# Digital_Fanout.net
KiCad netlist of a schematic drawn in Altium Designer
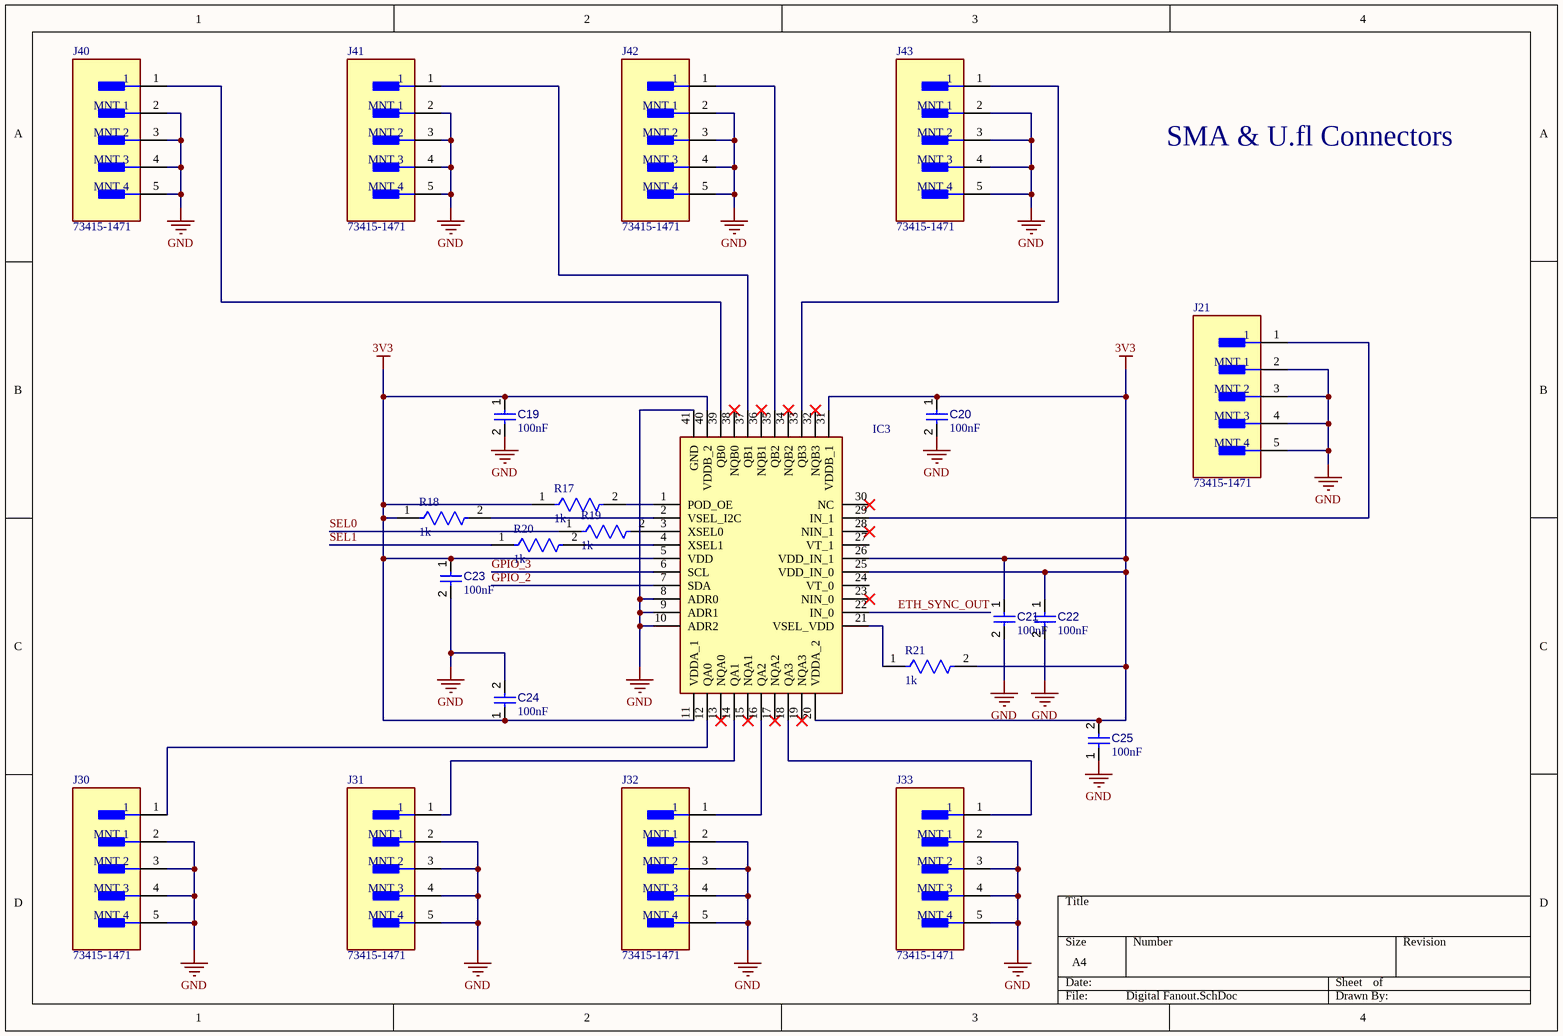
[diagram p0: Digital Fanout.SchDoc]

(export (version "E")
  (design (tool "Eeschema 10.0.6"))
  (components
    (comp (ref "C19")
      (value "100nF")
      (footprint "CAPC0402(1005)60_L")
      (description "Chip Capacitor, 100nF +/-20%, 25V, 0402, Thickness 0.6 mm")
      (fields (field (name "TOLERANCE") "10%") (field (name "Comment") "Capacitor 100nF +/-20% 25V 0402"))
      (libsource (lib "Lasse Johnsen") (part "CAP-NP-2"))
    )
    (comp (ref "C20")
      (value "100nF")
      (footprint "CAPC0402(1005)60_L")
      (description "Chip Capacitor, 100nF +/-20%, 25V, 0402, Thickness 0.6 mm")
      (fields (field (name "TOLERANCE") "10%") (field (name "Comment") "Capacitor 100nF +/-20% 25V 0402"))
      (libsource (lib "Lasse Johnsen") (part "CAP-NP-2"))
    )
    (comp (ref "C21")
      (value "100nF")
      (footprint "CAPC0402(1005)60_L")
      (description "Chip Capacitor, 100nF +/-20%, 25V, 0402, Thickness 0.6 mm")
      (fields (field (name "TOLERANCE") "10%") (field (name "Comment") "Capacitor 100nF +/-20% 25V 0402"))
      (libsource (lib "Lasse Johnsen") (part "CAP-NP-2"))
    )
    (comp (ref "C22")
      (value "100nF")
      (footprint "CAPC0402(1005)60_L")
      (description "Chip Capacitor, 100nF +/-20%, 25V, 0402, Thickness 0.6 mm")
      (fields (field (name "TOLERANCE") "10%") (field (name "Comment") "Capacitor 100nF +/-20% 25V 0402"))
      (libsource (lib "Lasse Johnsen") (part "CAP-NP-2"))
    )
    (comp (ref "C23")
      (value "100nF")
      (footprint "CAPC0402(1005)60_L")
      (description "Chip Capacitor, 100nF +/-20%, 25V, 0402, Thickness 0.6 mm")
      (fields (field (name "TOLERANCE") "10%") (field (name "Comment") "Capacitor 100nF +/-20% 25V 0402"))
      (libsource (lib "Lasse Johnsen") (part "CAP-NP-2"))
    )
    (comp (ref "C24")
      (value "100nF")
      (footprint "CAPC0402(1005)60_L")
      (description "Chip Capacitor, 100nF +/-20%, 25V, 0402, Thickness 0.6 mm")
      (fields (field (name "TOLERANCE") "10%") (field (name "Comment") "Capacitor 100nF +/-20% 25V 0402"))
      (libsource (lib "Lasse Johnsen") (part "CAP-NP-2"))
    )
    (comp (ref "C25")
      (value "100nF")
      (footprint "CAPC0402(1005)60_L")
      (description "Chip Capacitor, 100nF +/-20%, 25V, 0402, Thickness 0.6 mm")
      (fields (field (name "TOLERANCE") "10%") (field (name "Comment") "Capacitor 100nF +/-20% 25V 0402"))
      (libsource (lib "Lasse Johnsen") (part "CAP-NP-2"))
    )
    (comp (ref "IC3")
      (value "8T79S308NLGI")
      (footprint "SamacSys:QFN50P600X600X100-41N")
      (description "Integrated Circuit")
      (fields (field (name "MOUSER PART NUMBER") "972-8T79S308NLGI"))
      (libsource (lib "*") (part "8T79S308NLGI"))
    )
    (comp (ref "J21")
      (value "73415-1471")
      (footprint "FP-73415-1471-MFG")
      (description "CONN MMCX JACK STR 50 OHM PCB")
      (fields
        (field (name "MANUFACTURER") "Molex")
        (field (name "OCTOPART") "https://octopart.com/73415-1471-molex-776288")
      )
      (libsource (lib "Altium Content Vault") (part "e24f7cd101112e4466c0a3e46d8e956"))
    )
    (comp (ref "J30")
      (value "73415-1471")
      (footprint "FP-73415-1471-MFG")
      (description "CONN MMCX JACK STR 50 OHM PCB")
      (fields
        (field (name "MANUFACTURER") "Molex")
        (field (name "OCTOPART") "https://octopart.com/73415-1471-molex-776288")
      )
      (libsource (lib "Altium Content Vault") (part "e24f7cd101112e4466c0a3e46d8e956"))
    )
    (comp (ref "J31")
      (value "73415-1471")
      (footprint "FP-73415-1471-MFG")
      (description "CONN MMCX JACK STR 50 OHM PCB")
      (fields
        (field (name "MANUFACTURER") "Molex")
        (field (name "OCTOPART") "https://octopart.com/73415-1471-molex-776288")
      )
      (libsource (lib "Altium Content Vault") (part "e24f7cd101112e4466c0a3e46d8e956"))
    )
    (comp (ref "J32")
      (value "73415-1471")
      (footprint "FP-73415-1471-MFG")
      (description "CONN MMCX JACK STR 50 OHM PCB")
      (fields
        (field (name "MANUFACTURER") "Molex")
        (field (name "OCTOPART") "https://octopart.com/73415-1471-molex-776288")
      )
      (libsource (lib "Altium Content Vault") (part "e24f7cd101112e4466c0a3e46d8e956"))
    )
    (comp (ref "J33")
      (value "73415-1471")
      (footprint "FP-73415-1471-MFG")
      (description "CONN MMCX JACK STR 50 OHM PCB")
      (fields
        (field (name "MANUFACTURER") "Molex")
        (field (name "OCTOPART") "https://octopart.com/73415-1471-molex-776288")
      )
      (libsource (lib "Altium Content Vault") (part "e24f7cd101112e4466c0a3e46d8e956"))
    )
    (comp (ref "J40")
      (value "73415-1471")
      (footprint "FP-73415-1471-MFG")
      (description "CONN MMCX JACK STR 50 OHM PCB")
      (fields
        (field (name "MANUFACTURER") "Molex")
        (field (name "OCTOPART") "https://octopart.com/73415-1471-molex-776288")
      )
      (libsource (lib "Altium Content Vault") (part "e24f7cd101112e4466c0a3e46d8e956"))
    )
    (comp (ref "J41")
      (value "73415-1471")
      (footprint "FP-73415-1471-MFG")
      (description "CONN MMCX JACK STR 50 OHM PCB")
      (fields
        (field (name "MANUFACTURER") "Molex")
        (field (name "OCTOPART") "https://octopart.com/73415-1471-molex-776288")
      )
      (libsource (lib "Altium Content Vault") (part "e24f7cd101112e4466c0a3e46d8e956"))
    )
    (comp (ref "J42")
      (value "73415-1471")
      (footprint "FP-73415-1471-MFG")
      (description "CONN MMCX JACK STR 50 OHM PCB")
      (fields
        (field (name "MANUFACTURER") "Molex")
        (field (name "OCTOPART") "https://octopart.com/73415-1471-molex-776288")
      )
      (libsource (lib "Altium Content Vault") (part "e24f7cd101112e4466c0a3e46d8e956"))
    )
    (comp (ref "J43")
      (value "73415-1471")
      (footprint "FP-73415-1471-MFG")
      (description "CONN MMCX JACK STR 50 OHM PCB")
      (fields
        (field (name "MANUFACTURER") "Molex")
        (field (name "OCTOPART") "https://octopart.com/73415-1471-molex-776288")
      )
      (libsource (lib "Altium Content Vault") (part "e24f7cd101112e4466c0a3e46d8e956"))
    )
    (comp (ref "R17")
      (value "1k")
      (footprint "FP-CRCW0402-e3-MFG")
      (description "RES Thick Film, 1kΩ, 1%, 0.063W, 100ppm/°C, 0402")
      (fields (field (name "TOLERANCE") "1%"))
      (libsource (lib "Altium Content Vault") (part "1029c3af85768c4190bb7ad29bc67b5"))
    )
    (comp (ref "R18")
      (value "1k")
      (footprint "FP-CRCW0402-e3-MFG")
      (description "RES Thick Film, 1kΩ, 1%, 0.063W, 100ppm/°C, 0402")
      (fields (field (name "TOLERANCE") "1%"))
      (libsource (lib "Altium Content Vault") (part "1029c3af85768c4190bb7ad29bc67b5"))
    )
    (comp (ref "R19")
      (value "1k")
      (footprint "FP-CRCW0402-e3-MFG")
      (description "RES Thick Film, 1kΩ, 1%, 0.063W, 100ppm/°C, 0402")
      (fields (field (name "TOLERANCE") "1%"))
      (libsource (lib "Altium Content Vault") (part "1029c3af85768c4190bb7ad29bc67b5"))
    )
    (comp (ref "R20")
      (value "1k")
      (footprint "FP-CRCW0402-e3-MFG")
      (description "RES Thick Film, 1kΩ, 1%, 0.063W, 100ppm/°C, 0402")
      (fields (field (name "TOLERANCE") "1%"))
      (libsource (lib "Altium Content Vault") (part "1029c3af85768c4190bb7ad29bc67b5"))
    )
    (comp (ref "R21")
      (value "1k")
      (footprint "FP-CRCW0402-e3-MFG")
      (description "RES Thick Film, 1kΩ, 1%, 0.063W, 100ppm/°C, 0402")
      (fields (field (name "TOLERANCE") "1%"))
      (libsource (lib "Altium Content Vault") (part "1029c3af85768c4190bb7ad29bc67b5"))
    )
  )
  (nets
    (net (code "1") (name "/ETH_SYNC_OUT") (class "Default")
      (node (ref "IC3") (pin "22") (pinfunction "IN_0_22") (pintype "passive"))
    )
    (net (code "2") (name "/GPIO_2") (class "Default")
      (node (ref "IC3") (pin "7") (pinfunction "SDA_7") (pintype "passive"))
    )
    (net (code "3") (name "/GPIO_3") (class "Default")
      (node (ref "IC3") (pin "6") (pinfunction "SCL_6") (pintype "passive"))
    )
    (net (code "4") (name "/SEL0") (class "Default")
      (node (ref "R19") (pin "1") (pinfunction "1_1") (pintype "passive"))
    )
    (net (code "5") (name "/SEL1") (class "Default")
      (node (ref "R20") (pin "1") (pinfunction "1_1") (pintype "passive"))
    )
    (net (code "6") (name "3V3") (class "Default")
      (node (ref "C19") (pin "1") (pinfunction "1_1") (pintype "passive"))
      (node (ref "C20") (pin "1") (pinfunction "1_1") (pintype "passive"))
      (node (ref "C21") (pin "1") (pinfunction "1_1") (pintype "passive"))
      (node (ref "C22") (pin "1") (pinfunction "1_1") (pintype "passive"))
      (node (ref "C23") (pin "1") (pinfunction "1_1") (pintype "passive"))
      (node (ref "C24") (pin "1") (pinfunction "1_1") (pintype "passive"))
      (node (ref "C25") (pin "2") (pinfunction "2_2") (pintype "passive"))
      (node (ref "IC3") (pin "11") (pinfunction "VDDA_1_11") (pintype "passive"))
      (node (ref "IC3") (pin "20") (pinfunction "VDDA_2_20") (pintype "passive"))
      (node (ref "IC3") (pin "25") (pinfunction "VDD_IN_0_25") (pintype "passive"))
      (node (ref "IC3") (pin "26") (pinfunction "VDD_IN_1_26") (pintype "passive"))
      (node (ref "IC3") (pin "31") (pinfunction "VDDB_1_31") (pintype "passive"))
      (node (ref "IC3") (pin "40") (pinfunction "VDDB_2_40") (pintype "passive"))
      (node (ref "IC3") (pin "5") (pinfunction "VDD_5") (pintype "passive"))
      (node (ref "R17") (pin "1") (pinfunction "1_1") (pintype "passive"))
      (node (ref "R18") (pin "1") (pinfunction "1_1") (pintype "passive"))
      (node (ref "R21") (pin "2") (pinfunction "2_2") (pintype "passive"))
    )
    (net (code "7") (name "GND") (class "Default")
      (node (ref "C19") (pin "2") (pinfunction "2_2") (pintype "passive"))
      (node (ref "C20") (pin "2") (pinfunction "2_2") (pintype "passive"))
      (node (ref "C21") (pin "2") (pinfunction "2_2") (pintype "passive"))
      (node (ref "C22") (pin "2") (pinfunction "2_2") (pintype "passive"))
      (node (ref "C23") (pin "2") (pinfunction "2_2") (pintype "passive"))
      (node (ref "C24") (pin "2") (pinfunction "2_2") (pintype "passive"))
      (node (ref "C25") (pin "1") (pinfunction "1_1") (pintype "passive"))
      (node (ref "IC3") (pin "10") (pinfunction "ADR2_10") (pintype "passive"))
      (node (ref "IC3") (pin "41") (pinfunction "GND_41") (pintype "passive"))
      (node (ref "IC3") (pin "8") (pinfunction "ADR0_8") (pintype "passive"))
      (node (ref "IC3") (pin "9") (pinfunction "ADR1_9") (pintype "passive"))
      (node (ref "J21") (pin "2") (pinfunction "MNT_1_2") (pintype "passive"))
      (node (ref "J21") (pin "3") (pinfunction "MNT_2_3") (pintype "passive"))
      (node (ref "J21") (pin "4") (pinfunction "MNT_3_4") (pintype "passive"))
      (node (ref "J21") (pin "5") (pinfunction "MNT_4_5") (pintype "passive"))
      (node (ref "J30") (pin "2") (pinfunction "MNT_1_2") (pintype "passive"))
      (node (ref "J30") (pin "3") (pinfunction "MNT_2_3") (pintype "passive"))
      (node (ref "J30") (pin "4") (pinfunction "MNT_3_4") (pintype "passive"))
      (node (ref "J30") (pin "5") (pinfunction "MNT_4_5") (pintype "passive"))
      (node (ref "J31") (pin "2") (pinfunction "MNT_1_2") (pintype "passive"))
      (node (ref "J31") (pin "3") (pinfunction "MNT_2_3") (pintype "passive"))
      (node (ref "J31") (pin "4") (pinfunction "MNT_3_4") (pintype "passive"))
      (node (ref "J31") (pin "5") (pinfunction "MNT_4_5") (pintype "passive"))
      (node (ref "J32") (pin "2") (pinfunction "MNT_1_2") (pintype "passive"))
      (node (ref "J32") (pin "3") (pinfunction "MNT_2_3") (pintype "passive"))
      (node (ref "J32") (pin "4") (pinfunction "MNT_3_4") (pintype "passive"))
      (node (ref "J32") (pin "5") (pinfunction "MNT_4_5") (pintype "passive"))
      (node (ref "J33") (pin "2") (pinfunction "MNT_1_2") (pintype "passive"))
      (node (ref "J33") (pin "3") (pinfunction "MNT_2_3") (pintype "passive"))
      (node (ref "J33") (pin "4") (pinfunction "MNT_3_4") (pintype "passive"))
      (node (ref "J33") (pin "5") (pinfunction "MNT_4_5") (pintype "passive"))
      (node (ref "J40") (pin "2") (pinfunction "MNT_1_2") (pintype "passive"))
      (node (ref "J40") (pin "3") (pinfunction "MNT_2_3") (pintype "passive"))
      (node (ref "J40") (pin "4") (pinfunction "MNT_3_4") (pintype "passive"))
      (node (ref "J40") (pin "5") (pinfunction "MNT_4_5") (pintype "passive"))
      (node (ref "J41") (pin "2") (pinfunction "MNT_1_2") (pintype "passive"))
      (node (ref "J41") (pin "3") (pinfunction "MNT_2_3") (pintype "passive"))
      (node (ref "J41") (pin "4") (pinfunction "MNT_3_4") (pintype "passive"))
      (node (ref "J41") (pin "5") (pinfunction "MNT_4_5") (pintype "passive"))
      (node (ref "J42") (pin "2") (pinfunction "MNT_1_2") (pintype "passive"))
      (node (ref "J42") (pin "3") (pinfunction "MNT_2_3") (pintype "passive"))
      (node (ref "J42") (pin "4") (pinfunction "MNT_3_4") (pintype "passive"))
      (node (ref "J42") (pin "5") (pinfunction "MNT_4_5") (pintype "passive"))
      (node (ref "J43") (pin "2") (pinfunction "MNT_1_2") (pintype "passive"))
      (node (ref "J43") (pin "3") (pinfunction "MNT_2_3") (pintype "passive"))
      (node (ref "J43") (pin "4") (pinfunction "MNT_3_4") (pintype "passive"))
      (node (ref "J43") (pin "5") (pinfunction "MNT_4_5") (pintype "passive"))
    )
    (net (code "8") (name "Net-(IC3-IN_1)") (class "Default")
      (node (ref "IC3") (pin "29") (pinfunction "IN_1_29") (pintype "passive"))
      (node (ref "J21") (pin "1") (pinfunction "1_1") (pintype "passive"))
    )
    (net (code "9") (name "Net-(IC3-POD_OE)") (class "Default")
      (node (ref "IC3") (pin "1") (pinfunction "POD_OE_1") (pintype "passive"))
      (node (ref "R17") (pin "2") (pinfunction "2_2") (pintype "passive"))
    )
    (net (code "10") (name "Net-(IC3-QA0)") (class "Default")
      (node (ref "IC3") (pin "12") (pinfunction "QA0_12") (pintype "passive"))
      (node (ref "J30") (pin "1") (pinfunction "1_1") (pintype "passive"))
    )
    (net (code "11") (name "Net-(IC3-QA1)") (class "Default")
      (node (ref "IC3") (pin "14") (pinfunction "QA1_14") (pintype "passive"))
      (node (ref "J31") (pin "1") (pinfunction "1_1") (pintype "passive"))
    )
    (net (code "12") (name "Net-(IC3-QA2)") (class "Default")
      (node (ref "IC3") (pin "16") (pinfunction "QA2_16") (pintype "passive"))
      (node (ref "J32") (pin "1") (pinfunction "1_1") (pintype "passive"))
    )
    (net (code "13") (name "Net-(IC3-QA3)") (class "Default")
      (node (ref "IC3") (pin "18") (pinfunction "QA3_18") (pintype "passive"))
      (node (ref "J33") (pin "1") (pinfunction "1_1") (pintype "passive"))
    )
    (net (code "14") (name "Net-(IC3-QB0)") (class "Default")
      (node (ref "IC3") (pin "39") (pinfunction "QB0_39") (pintype "passive"))
      (node (ref "J40") (pin "1") (pinfunction "1_1") (pintype "passive"))
    )
    (net (code "15") (name "Net-(IC3-QB1)") (class "Default")
      (node (ref "IC3") (pin "37") (pinfunction "QB1_37") (pintype "passive"))
      (node (ref "J41") (pin "1") (pinfunction "1_1") (pintype "passive"))
    )
    (net (code "16") (name "Net-(IC3-QB2)") (class "Default")
      (node (ref "IC3") (pin "35") (pinfunction "QB2_35") (pintype "passive"))
      (node (ref "J42") (pin "1") (pinfunction "1_1") (pintype "passive"))
    )
    (net (code "17") (name "Net-(IC3-QB3)") (class "Default")
      (node (ref "IC3") (pin "33") (pinfunction "QB3_33") (pintype "passive"))
      (node (ref "J43") (pin "1") (pinfunction "1_1") (pintype "passive"))
    )
    (net (code "18") (name "Net-(IC3-VSEL_I2C)") (class "Default")
      (node (ref "IC3") (pin "2") (pinfunction "VSEL_I2C_2") (pintype "passive"))
      (node (ref "R18") (pin "2") (pinfunction "2_2") (pintype "passive"))
    )
    (net (code "19") (name "Net-(IC3-VSEL_VDD)") (class "Default")
      (node (ref "IC3") (pin "21") (pinfunction "VSEL_VDD_21") (pintype "passive"))
      (node (ref "R21") (pin "1") (pinfunction "1_1") (pintype "passive"))
    )
    (net (code "20") (name "Net-(IC3-XSEL0)") (class "Default")
      (node (ref "IC3") (pin "3") (pinfunction "XSEL0_3") (pintype "passive"))
      (node (ref "R19") (pin "2") (pinfunction "2_2") (pintype "passive"))
    )
    (net (code "21") (name "Net-(IC3-XSEL1)") (class "Default")
      (node (ref "IC3") (pin "4") (pinfunction "XSEL1_4") (pintype "passive"))
      (node (ref "R20") (pin "2") (pinfunction "2_2") (pintype "passive"))
    )
    (net (code "22") (name "unconnected-(IC3-NC-Pad30)") (class "Default")
      (node (ref "IC3") (pin "30") (pinfunction "NC_30") (pintype "passive+no_connect"))
    )
    (net (code "23") (name "unconnected-(IC3-NIN_0-Pad23)") (class "Default")
      (node (ref "IC3") (pin "23") (pinfunction "NIN_0_23") (pintype "passive+no_connect"))
    )
    (net (code "24") (name "unconnected-(IC3-NIN_1-Pad28)") (class "Default")
      (node (ref "IC3") (pin "28") (pinfunction "NIN_1_28") (pintype "passive+no_connect"))
    )
    (net (code "25") (name "unconnected-(IC3-NQA0-Pad13)") (class "Default")
      (node (ref "IC3") (pin "13") (pinfunction "NQA0_13") (pintype "passive+no_connect"))
    )
    (net (code "26") (name "unconnected-(IC3-NQA1-Pad15)") (class "Default")
      (node (ref "IC3") (pin "15") (pinfunction "NQA1_15") (pintype "passive+no_connect"))
    )
    (net (code "27") (name "unconnected-(IC3-NQA2-Pad17)") (class "Default")
      (node (ref "IC3") (pin "17") (pinfunction "NQA2_17") (pintype "passive+no_connect"))
    )
    (net (code "28") (name "unconnected-(IC3-NQA3-Pad19)") (class "Default")
      (node (ref "IC3") (pin "19") (pinfunction "NQA3_19") (pintype "passive+no_connect"))
    )
    (net (code "29") (name "unconnected-(IC3-NQB0-Pad38)") (class "Default")
      (node (ref "IC3") (pin "38") (pinfunction "NQB0_38") (pintype "passive+no_connect"))
    )
    (net (code "30") (name "unconnected-(IC3-NQB1-Pad36)") (class "Default")
      (node (ref "IC3") (pin "36") (pinfunction "NQB1_36") (pintype "passive+no_connect"))
    )
    (net (code "31") (name "unconnected-(IC3-NQB2-Pad34)") (class "Default")
      (node (ref "IC3") (pin "34") (pinfunction "NQB2_34") (pintype "passive+no_connect"))
    )
    (net (code "32") (name "unconnected-(IC3-NQB3-Pad32)") (class "Default")
      (node (ref "IC3") (pin "32") (pinfunction "NQB3_32") (pintype "passive+no_connect"))
    )
    (net (code "33") (name "unconnected-(IC3-VT_0-Pad24)") (class "Default")
      (node (ref "IC3") (pin "24") (pinfunction "VT_0_24") (pintype "passive"))
    )
    (net (code "34") (name "unconnected-(IC3-VT_1-Pad27)") (class "Default")
      (node (ref "IC3") (pin "27") (pinfunction "VT_1_27") (pintype "passive"))
    )
  )
)
